# New_Project_2024-09-24_23-01-51.net
KiCad netlist of a schematic drawn in EasyEDA Pro
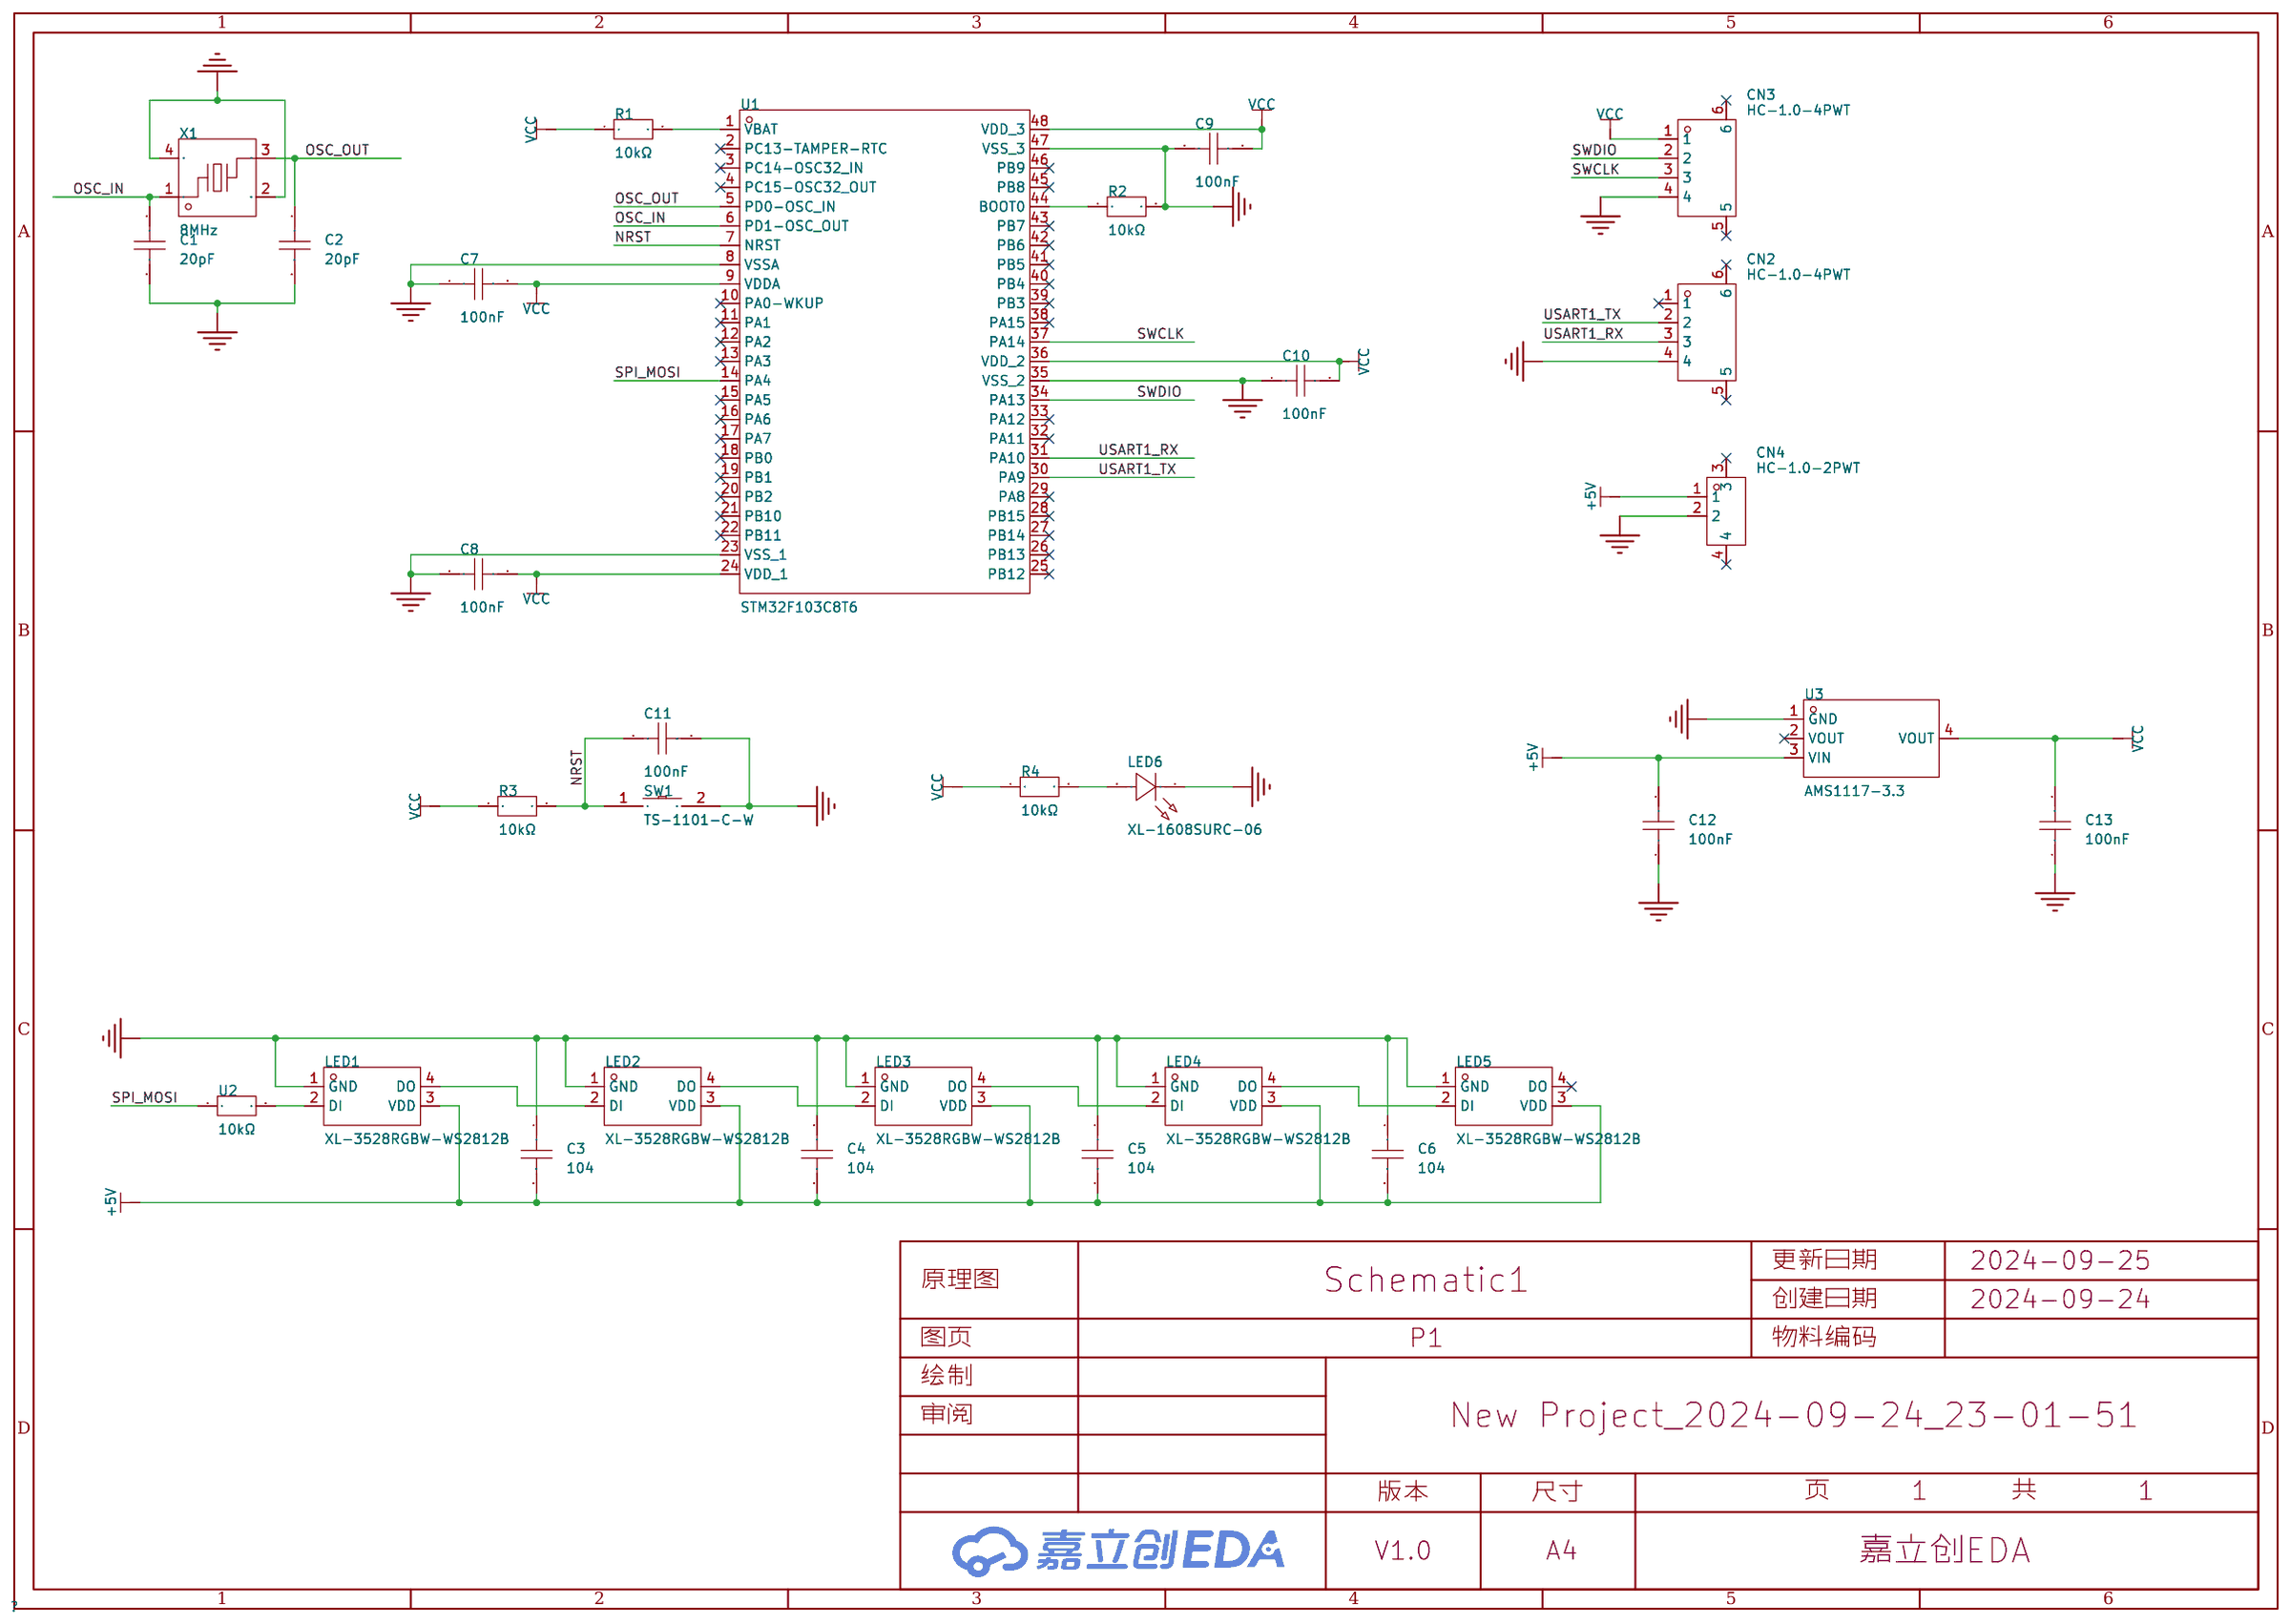
[diagram p0: schematic sheet]

(export (version "E")
  (design (tool "Eeschema 10.0.6"))
  (components
    (comp (ref "C1")
      (value "20pF")
      (footprint "easyedapro:C0603")
      (description "容值:100nF;精度:±10%;额定电压:50V;材质(温度系数):X7R;")
      (fields
        (field (name "Manufacturer Part") "CGA0603X7R104K500JT")
        (field (name "Manufacturer") "HRE(芯声)")
      )
      (libsource (lib "easyedapro") (part "CGA0603X7R104K500JT"))
    )
    (comp (ref "C2")
      (value "20pF")
      (footprint "easyedapro:C0603")
      (description "容值:100nF;精度:±10%;额定电压:50V;材质(温度系数):X7R;")
      (fields
        (field (name "Manufacturer Part") "CGA0603X7R104K500JT")
        (field (name "Manufacturer") "HRE(芯声)")
      )
      (libsource (lib "easyedapro") (part "CGA0603X7R104K500JT"))
    )
    (comp (ref "C3")
      (value "104")
      (footprint "easyedapro:C0603")
      (description "容值:100nF;精度:±10%;额定电压:50V;材质(温度系数):X7R;")
      (fields
        (field (name "Manufacturer Part") "CGA0603X7R104K500JT")
        (field (name "Manufacturer") "HRE(芯声)")
      )
      (libsource (lib "easyedapro") (part "CGA0603X7R104K500JT"))
    )
    (comp (ref "C4")
      (value "104")
      (footprint "easyedapro:C0603")
      (description "容值:100nF;精度:±10%;额定电压:50V;材质(温度系数):X7R;")
      (fields
        (field (name "Manufacturer Part") "CGA0603X7R104K500JT")
        (field (name "Manufacturer") "HRE(芯声)")
      )
      (libsource (lib "easyedapro") (part "CGA0603X7R104K500JT"))
    )
    (comp (ref "C5")
      (value "104")
      (footprint "easyedapro:C0603")
      (description "容值:100nF;精度:±10%;额定电压:50V;材质(温度系数):X7R;")
      (fields
        (field (name "Manufacturer Part") "CGA0603X7R104K500JT")
        (field (name "Manufacturer") "HRE(芯声)")
      )
      (libsource (lib "easyedapro") (part "CGA0603X7R104K500JT"))
    )
    (comp (ref "C6")
      (value "104")
      (footprint "easyedapro:C0603")
      (description "容值:100nF;精度:±10%;额定电压:50V;材质(温度系数):X7R;")
      (fields
        (field (name "Manufacturer Part") "CGA0603X7R104K500JT")
        (field (name "Manufacturer") "HRE(芯声)")
      )
      (libsource (lib "easyedapro") (part "CGA0603X7R104K500JT"))
    )
    (comp (ref "C7")
      (value "100nF")
      (footprint "easyedapro:C0603")
      (description "容值:100nF;精度:±10%;额定电压:50V;材质(温度系数):X7R;")
      (fields
        (field (name "Manufacturer Part") "CGA0603X7R104K500JT")
        (field (name "Manufacturer") "HRE(芯声)")
      )
      (libsource (lib "easyedapro") (part "CGA0603X7R104K500JT"))
    )
    (comp (ref "C8")
      (value "100nF")
      (footprint "easyedapro:C0603")
      (description "容值:100nF;精度:±10%;额定电压:50V;材质(温度系数):X7R;")
      (fields
        (field (name "Manufacturer Part") "CGA0603X7R104K500JT")
        (field (name "Manufacturer") "HRE(芯声)")
      )
      (libsource (lib "easyedapro") (part "CGA0603X7R104K500JT"))
    )
    (comp (ref "C9")
      (value "100nF")
      (footprint "easyedapro:C0603")
      (description "容值:100nF;精度:±10%;额定电压:50V;材质(温度系数):X7R;")
      (fields
        (field (name "Manufacturer Part") "CGA0603X7R104K500JT")
        (field (name "Manufacturer") "HRE(芯声)")
      )
      (libsource (lib "easyedapro") (part "CGA0603X7R104K500JT"))
    )
    (comp (ref "C10")
      (value "100nF")
      (footprint "easyedapro:C0603")
      (description "容值:100nF;精度:±10%;额定电压:50V;材质(温度系数):X7R;")
      (fields
        (field (name "Manufacturer Part") "CGA0603X7R104K500JT")
        (field (name "Manufacturer") "HRE(芯声)")
      )
      (libsource (lib "easyedapro") (part "CGA0603X7R104K500JT"))
    )
    (comp (ref "C11")
      (value "100nF")
      (footprint "easyedapro:C0603")
      (description "容值:100nF;精度:±10%;额定电压:50V;材质(温度系数):X7R;")
      (fields
        (field (name "Manufacturer Part") "CGA0603X7R104K500JT")
        (field (name "Manufacturer") "HRE(芯声)")
      )
      (libsource (lib "easyedapro") (part "CGA0603X7R104K500JT"))
    )
    (comp (ref "C12")
      (value "100nF")
      (footprint "easyedapro:C0603")
      (description "容值:100nF;精度:±10%;额定电压:50V;材质(温度系数):X7R;")
      (fields
        (field (name "Manufacturer Part") "CGA0603X7R104K500JT")
        (field (name "Manufacturer") "HRE(芯声)")
      )
      (libsource (lib "easyedapro") (part "CGA0603X7R104K500JT"))
    )
    (comp (ref "C13")
      (value "100nF")
      (footprint "easyedapro:C0603")
      (description "容值:100nF;精度:±10%;额定电压:50V;材质(温度系数):X7R;")
      (fields
        (field (name "Manufacturer Part") "CGA0603X7R104K500JT")
        (field (name "Manufacturer") "HRE(芯声)")
      )
      (libsource (lib "easyedapro") (part "CGA0603X7R104K500JT"))
    )
    (comp (ref "CN2")
      (value "HC-1.0-4PWT")
      (footprint "easyedapro:CONN-SMD_4P-P1.00_HCTL_HC-1.0-4PWT")
      (fields (field (name "Manufacturer") "HCTL(华灿天禄)"))
      (libsource (lib "easyedapro") (part "HC-1.0-4PWT"))
    )
    (comp (ref "CN3")
      (value "HC-1.0-4PWT")
      (footprint "easyedapro:CONN-SMD_4P-P1.00_HCTL_HC-1.0-4PWT")
      (fields (field (name "Manufacturer") "HCTL(华灿天禄)"))
      (libsource (lib "easyedapro") (part "HC-1.0-4PWT"))
    )
    (comp (ref "CN4")
      (value "HC-1.0-2PWT")
      (footprint "easyedapro:CONN-SMD_HC-1.0-2PWT")
      (fields (field (name "Manufacturer") "HCTL(华灿天禄)"))
      (libsource (lib "easyedapro") (part "HC-1.0-2PWT"))
    )
    (comp (ref "LED1")
      (value "XL-3528RGBW-WS2812B")
      (footprint "easyedapro:LED-SMD_4P-L3.5-W2.8-BR-1")
      (description "3528 七彩幻彩雾状 ws2812B 内置驱动IC")
      (fields (field (name "Manufacturer") "XINGLIGHT(成兴光)"))
      (libsource (lib "easyedapro") (part "XL-3528RGBW-WS2812B"))
    )
    (comp (ref "LED2")
      (value "XL-3528RGBW-WS2812B")
      (footprint "easyedapro:LED-SMD_4P-L3.5-W2.8-BR-1")
      (description "3528 七彩幻彩雾状 ws2812B 内置驱动IC")
      (fields (field (name "Manufacturer") "XINGLIGHT(成兴光)"))
      (libsource (lib "easyedapro") (part "XL-3528RGBW-WS2812B"))
    )
    (comp (ref "LED3")
      (value "XL-3528RGBW-WS2812B")
      (footprint "easyedapro:LED-SMD_4P-L3.5-W2.8-BR-1")
      (description "3528 七彩幻彩雾状 ws2812B 内置驱动IC")
      (fields (field (name "Manufacturer") "XINGLIGHT(成兴光)"))
      (libsource (lib "easyedapro") (part "XL-3528RGBW-WS2812B"))
    )
    (comp (ref "LED4")
      (value "XL-3528RGBW-WS2812B")
      (footprint "easyedapro:LED-SMD_4P-L3.5-W2.8-BR-1")
      (description "3528 七彩幻彩雾状 ws2812B 内置驱动IC")
      (fields (field (name "Manufacturer") "XINGLIGHT(成兴光)"))
      (libsource (lib "easyedapro") (part "XL-3528RGBW-WS2812B"))
    )
    (comp (ref "LED5")
      (value "XL-3528RGBW-WS2812B")
      (footprint "easyedapro:LED-SMD_4P-L3.5-W2.8-BR-1")
      (description "3528 七彩幻彩雾状 ws2812B 内置驱动IC")
      (fields (field (name "Manufacturer") "XINGLIGHT(成兴光)"))
      (libsource (lib "easyedapro") (part "XL-3528RGBW-WS2812B"))
    )
    (comp (ref "LED6")
      (value "XL-1608SURC-06")
      (footprint "easyedapro:LED0603-RD_RED")
      (description "发光颜色:红色;功率:55mW;正向电流:25mA;主波长:617nm~621nm;透镜颜色:无色透明透镜;色温:-;发光角度:120°;载带方式:正贴;工作温度:-30°C~+85°C;")
      (fields (field (name "Manufacturer") "XINGLIGHT(成兴光)"))
      (libsource (lib "easyedapro") (part "XL-1608SURC-06"))
    )
    (comp (ref "R1")
      (value "10kΩ")
      (footprint "easyedapro:R0603")
      (description "电阻类型:厚膜电阻;阻值:4.7kΩ;精度:±5%;功率:100mW;最大工作电压:75V;温度系数:±100ppm/°C;")
      (fields (field (name "Manufacturer Part") "FRC0603J472 TS") (field (name "Manufacturer") "FOJAN(富捷)"))
      (libsource (lib "easyedapro") (part "FRC0603J472 TS"))
    )
    (comp (ref "R2")
      (value "10kΩ")
      (footprint "easyedapro:R0603")
      (description "电阻类型:厚膜电阻;阻值:4.7kΩ;精度:±5%;功率:100mW;最大工作电压:75V;温度系数:±100ppm/°C;")
      (fields (field (name "Manufacturer Part") "FRC0603J472 TS") (field (name "Manufacturer") "FOJAN(富捷)"))
      (libsource (lib "easyedapro") (part "FRC0603J472 TS"))
    )
    (comp (ref "R3")
      (value "10kΩ")
      (footprint "easyedapro:R0603")
      (description "电阻类型:厚膜电阻;阻值:4.7kΩ;精度:±5%;功率:100mW;最大工作电压:75V;温度系数:±100ppm/°C;")
      (fields (field (name "Manufacturer Part") "FRC0603J472 TS") (field (name "Manufacturer") "FOJAN(富捷)"))
      (libsource (lib "easyedapro") (part "FRC0603J472 TS"))
    )
    (comp (ref "R4")
      (value "10kΩ")
      (footprint "easyedapro:R0603")
      (description "电阻类型:厚膜电阻;阻值:4.7kΩ;精度:±5%;功率:100mW;最大工作电压:75V;温度系数:±100ppm/°C;")
      (fields (field (name "Manufacturer Part") "FRC0603J472 TS") (field (name "Manufacturer") "FOJAN(富捷)"))
      (libsource (lib "easyedapro") (part "FRC0603J472 TS"))
    )
    (comp (ref "SW1")
      (value "TS-1101-C-W")
      (footprint "easyedapro:SW-SMD_L6.0-W3.3-LS8.0")
      (fields (field (name "Manufacturer") "XKB Connectivity(中国星坤)"))
      (libsource (lib "easyedapro") (part "TS-1101-C-W"))
    )
    (comp (ref "U1")
      (value "STM32F103C8T6")
      (footprint "easyedapro:LQFP-48_L7.0-W7.0-P0.50-LS9.0-BL")
      (description "CPU内核:ARM-M3;程序存储容量:64KB;RAM总容量:20KB;GPIO端口数量:37;工作电压范围:2V~3.6V;CPU最大主频:72MHz;程序存储器类型:FLASH;")
      (fields (field (name "Manufacturer") "ST(意法半导体)"))
      (libsource (lib "easyedapro") (part "STM32F103C8T6"))
    )
    (comp (ref "U2")
      (value "10kΩ")
      (footprint "easyedapro:R0603")
      (description "电阻类型:厚膜电阻;阻值:390kΩ;精度:±1%;功率:100mW;最大工作电压:75V;温度系数:±100ppm/°C;")
      (fields (field (name "Manufacturer Part") "FRC0603F3903TS") (field (name "Manufacturer") "FOJAN(富捷)"))
      (libsource (lib "easyedapro") (part "FRC0603F3903TS"))
    )
    (comp (ref "U3")
      (value "AMS1117-3.3")
      (footprint "easyedapro:SOT-223-3_L6.5-W3.4-P2.30-LS7.0-BR")
      (description "输出类型:固定;最大输入电压:-;输出电压:3.3V;最大输出电流:1A;电源纹波抑制比(PSRR):72dB@(120Hz);输出极性:正极;")
      (fields (field (name "Manufacturer") "AMS"))
      (libsource (lib "easyedapro") (part "AMS1117-3.3"))
    )
    (comp (ref "X1")
      (value "8MHz")
      (footprint "easyedapro:OSC-SMD_4P-L3.2-W2.5-BL")
      (description "晶振类型:贴片晶振;频率:8MHz;常温频差:±10ppm;外接负载电容:12pF;频率稳定度(全温):±20ppm;")
      (fields (field (name "Manufacturer Part") "X32258MOB4SI") (field (name "Manufacturer") "YXC(扬兴晶振)"))
      (libsource (lib "easyedapro") (part "x32258mob4si"))
    )
  )
  (nets
    (net (code "1") (name "+5V") (class "Default")
      (node (ref "C12") (pin "2") (pinfunction "2_2") (pintype "unspecified"))
      (node (ref "C3") (pin "2") (pinfunction "2_2") (pintype "unspecified"))
      (node (ref "C4") (pin "2") (pinfunction "2_2") (pintype "unspecified"))
      (node (ref "C5") (pin "2") (pinfunction "2_2") (pintype "unspecified"))
      (node (ref "C6") (pin "2") (pinfunction "2_2") (pintype "unspecified"))
      (node (ref "CN4") (pin "1") (pinfunction "1_1") (pintype "unspecified"))
      (node (ref "LED1") (pin "3") (pinfunction "VDD_3") (pintype "unspecified"))
      (node (ref "LED2") (pin "3") (pinfunction "VDD_3") (pintype "unspecified"))
      (node (ref "LED3") (pin "3") (pinfunction "VDD_3") (pintype "unspecified"))
      (node (ref "LED4") (pin "3") (pinfunction "VDD_3") (pintype "unspecified"))
      (node (ref "LED5") (pin "3") (pinfunction "VDD_3") (pintype "unspecified"))
      (node (ref "U3") (pin "3") (pinfunction "VIN_3") (pintype "unspecified"))
    )
    (net (code "2") (name "/NRST") (class "Default")
      (node (ref "C11") (pin "1") (pinfunction "1_1") (pintype "unspecified"))
      (node (ref "R3") (pin "2") (pinfunction "2_2") (pintype "unspecified"))
      (node (ref "SW1") (pin "1") (pinfunction "1_1") (pintype "unspecified"))
      (node (ref "U1") (pin "7") (pinfunction "NRST_7") (pintype "unspecified"))
    )
    (net (code "3") (name "/OSC_IN") (class "Default")
      (node (ref "C1") (pin "1") (pinfunction "1_1") (pintype "unspecified"))
      (node (ref "U1") (pin "6") (pinfunction "PD1-OSC_OUT_6") (pintype "unspecified"))
      (node (ref "X1") (pin "1") (pinfunction "1_1") (pintype "input"))
    )
    (net (code "4") (name "/OSC_OUT") (class "Default")
      (node (ref "C2") (pin "1") (pinfunction "1_1") (pintype "unspecified"))
      (node (ref "U1") (pin "5") (pinfunction "PD0-OSC_IN_5") (pintype "unspecified"))
      (node (ref "X1") (pin "3") (pinfunction "3_3") (pintype "input"))
    )
    (net (code "5") (name "/SPI_MOSI") (class "Default")
      (node (ref "U1") (pin "14") (pinfunction "PA4_14") (pintype "unspecified"))
      (node (ref "U2") (pin "1") (pinfunction "1_1") (pintype "unspecified"))
    )
    (net (code "6") (name "/SWCLK") (class "Default")
      (node (ref "CN3") (pin "3") (pinfunction "3_3") (pintype "unspecified"))
      (node (ref "U1") (pin "37") (pinfunction "PA14_37") (pintype "unspecified"))
    )
    (net (code "7") (name "/SWDIO") (class "Default")
      (node (ref "CN3") (pin "2") (pinfunction "2_2") (pintype "unspecified"))
      (node (ref "U1") (pin "34") (pinfunction "PA13_34") (pintype "unspecified"))
    )
    (net (code "8") (name "/USART1_RX") (class "Default")
      (node (ref "CN2") (pin "3") (pinfunction "3_3") (pintype "unspecified"))
      (node (ref "U1") (pin "31") (pinfunction "PA10_31") (pintype "unspecified"))
    )
    (net (code "9") (name "/USART1_TX") (class "Default")
      (node (ref "CN2") (pin "2") (pinfunction "2_2") (pintype "unspecified"))
      (node (ref "U1") (pin "30") (pinfunction "PA9_30") (pintype "unspecified"))
    )
    (net (code "10") (name "GND") (class "Default")
      (node (ref "C1") (pin "2") (pinfunction "2_2") (pintype "unspecified"))
      (node (ref "C10") (pin "1") (pinfunction "1_1") (pintype "unspecified"))
      (node (ref "C11") (pin "2") (pinfunction "2_2") (pintype "unspecified"))
      (node (ref "C12") (pin "1") (pinfunction "1_1") (pintype "unspecified"))
      (node (ref "C13") (pin "1") (pinfunction "1_1") (pintype "unspecified"))
      (node (ref "C2") (pin "2") (pinfunction "2_2") (pintype "unspecified"))
      (node (ref "C3") (pin "1") (pinfunction "1_1") (pintype "unspecified"))
      (node (ref "C4") (pin "1") (pinfunction "1_1") (pintype "unspecified"))
      (node (ref "C5") (pin "1") (pinfunction "1_1") (pintype "unspecified"))
      (node (ref "C6") (pin "1") (pinfunction "1_1") (pintype "unspecified"))
      (node (ref "C7") (pin "1") (pinfunction "1_1") (pintype "unspecified"))
      (node (ref "C8") (pin "1") (pinfunction "1_1") (pintype "unspecified"))
      (node (ref "C9") (pin "1") (pinfunction "1_1") (pintype "unspecified"))
      (node (ref "CN2") (pin "4") (pinfunction "4_4") (pintype "unspecified"))
      (node (ref "CN3") (pin "4") (pinfunction "4_4") (pintype "unspecified"))
      (node (ref "CN4") (pin "2") (pinfunction "2_2") (pintype "unspecified"))
      (node (ref "LED1") (pin "1") (pinfunction "GND_1") (pintype "unspecified"))
      (node (ref "LED2") (pin "1") (pinfunction "GND_1") (pintype "unspecified"))
      (node (ref "LED3") (pin "1") (pinfunction "GND_1") (pintype "unspecified"))
      (node (ref "LED4") (pin "1") (pinfunction "GND_1") (pintype "unspecified"))
      (node (ref "LED5") (pin "1") (pinfunction "GND_1") (pintype "unspecified"))
      (node (ref "LED6") (pin "1") (pinfunction "K_1") (pintype "unspecified"))
      (node (ref "R2") (pin "2") (pinfunction "2_2") (pintype "unspecified"))
      (node (ref "SW1") (pin "2") (pinfunction "2_2") (pintype "unspecified"))
      (node (ref "U1") (pin "23") (pinfunction "VSS_1_23") (pintype "unspecified"))
      (node (ref "U1") (pin "35") (pinfunction "VSS_2_35") (pintype "unspecified"))
      (node (ref "U1") (pin "47") (pinfunction "VSS_3_47") (pintype "unspecified"))
      (node (ref "U1") (pin "8") (pinfunction "VSSA_8") (pintype "unspecified"))
      (node (ref "U3") (pin "1") (pinfunction "GND_1") (pintype "unspecified"))
      (node (ref "X1") (pin "2") (pinfunction "GND_2") (pintype "input"))
      (node (ref "X1") (pin "4") (pinfunction "GND_4") (pintype "input"))
    )
    (net (code "11") (name "Net-(LED1-DI)") (class "Default")
      (node (ref "LED1") (pin "2") (pinfunction "DI_2") (pintype "unspecified"))
      (node (ref "U2") (pin "2") (pinfunction "2_2") (pintype "unspecified"))
    )
    (net (code "12") (name "Net-(LED1-DO)") (class "Default")
      (node (ref "LED1") (pin "4") (pinfunction "DO_4") (pintype "unspecified"))
      (node (ref "LED2") (pin "2") (pinfunction "DI_2") (pintype "unspecified"))
    )
    (net (code "13") (name "Net-(LED2-DO)") (class "Default")
      (node (ref "LED2") (pin "4") (pinfunction "DO_4") (pintype "unspecified"))
      (node (ref "LED3") (pin "2") (pinfunction "DI_2") (pintype "unspecified"))
    )
    (net (code "14") (name "Net-(LED3-DO)") (class "Default")
      (node (ref "LED3") (pin "4") (pinfunction "DO_4") (pintype "unspecified"))
      (node (ref "LED4") (pin "2") (pinfunction "DI_2") (pintype "unspecified"))
    )
    (net (code "15") (name "Net-(LED4-DO)") (class "Default")
      (node (ref "LED4") (pin "4") (pinfunction "DO_4") (pintype "unspecified"))
      (node (ref "LED5") (pin "2") (pinfunction "DI_2") (pintype "unspecified"))
    )
    (net (code "16") (name "Net-(LED6-A)") (class "Default")
      (node (ref "LED6") (pin "2") (pinfunction "A_2") (pintype "unspecified"))
      (node (ref "R4") (pin "2") (pinfunction "2_2") (pintype "unspecified"))
    )
    (net (code "17") (name "Net-(U1-BOOT0)") (class "Default")
      (node (ref "R2") (pin "1") (pinfunction "1_1") (pintype "unspecified"))
      (node (ref "U1") (pin "44") (pinfunction "BOOT0_44") (pintype "unspecified"))
    )
    (net (code "18") (name "Net-(U1-VBAT)") (class "Default")
      (node (ref "R1") (pin "2") (pinfunction "2_2") (pintype "unspecified"))
      (node (ref "U1") (pin "1") (pinfunction "VBAT_1") (pintype "unspecified"))
    )
    (net (code "19") (name "VCC") (class "Default")
      (node (ref "C10") (pin "2") (pinfunction "2_2") (pintype "unspecified"))
      (node (ref "C13") (pin "2") (pinfunction "2_2") (pintype "unspecified"))
      (node (ref "C7") (pin "2") (pinfunction "2_2") (pintype "unspecified"))
      (node (ref "C8") (pin "2") (pinfunction "2_2") (pintype "unspecified"))
      (node (ref "C9") (pin "2") (pinfunction "2_2") (pintype "unspecified"))
      (node (ref "CN3") (pin "1") (pinfunction "1_1") (pintype "unspecified"))
      (node (ref "R1") (pin "1") (pinfunction "1_1") (pintype "unspecified"))
      (node (ref "R3") (pin "1") (pinfunction "1_1") (pintype "unspecified"))
      (node (ref "R4") (pin "1") (pinfunction "1_1") (pintype "unspecified"))
      (node (ref "U1") (pin "24") (pinfunction "VDD_1_24") (pintype "unspecified"))
      (node (ref "U1") (pin "36") (pinfunction "VDD_2_36") (pintype "unspecified"))
      (node (ref "U1") (pin "48") (pinfunction "VDD_3_48") (pintype "unspecified"))
      (node (ref "U1") (pin "9") (pinfunction "VDDA_9") (pintype "unspecified"))
      (node (ref "U3") (pin "4") (pinfunction "VOUT_4") (pintype "unspecified"))
    )
    (net (code "20") (name "unconnected-(CN2-Pad1)") (class "Default")
      (node (ref "CN2") (pin "1") (pinfunction "1_1") (pintype "unspecified+no_connect"))
    )
    (net (code "21") (name "unconnected-(CN2-Pad5)") (class "Default")
      (node (ref "CN2") (pin "5") (pinfunction "5_5") (pintype "unspecified+no_connect"))
    )
    (net (code "22") (name "unconnected-(CN2-Pad6)") (class "Default")
      (node (ref "CN2") (pin "6") (pinfunction "6_6") (pintype "unspecified+no_connect"))
    )
    (net (code "23") (name "unconnected-(CN3-Pad5)") (class "Default")
      (node (ref "CN3") (pin "5") (pinfunction "5_5") (pintype "unspecified+no_connect"))
    )
    (net (code "24") (name "unconnected-(CN3-Pad6)") (class "Default")
      (node (ref "CN3") (pin "6") (pinfunction "6_6") (pintype "unspecified+no_connect"))
    )
    (net (code "25") (name "unconnected-(CN4-Pad3)") (class "Default")
      (node (ref "CN4") (pin "3") (pinfunction "3_3") (pintype "unspecified+no_connect"))
    )
    (net (code "26") (name "unconnected-(CN4-Pad4)") (class "Default")
      (node (ref "CN4") (pin "4") (pinfunction "4_4") (pintype "unspecified+no_connect"))
    )
    (net (code "27") (name "unconnected-(LED5-DO-Pad4)") (class "Default")
      (node (ref "LED5") (pin "4") (pinfunction "DO_4") (pintype "unspecified+no_connect"))
    )
    (net (code "28") (name "unconnected-(U1-PA0-WKUP-Pad10)") (class "Default")
      (node (ref "U1") (pin "10") (pinfunction "PA0-WKUP_10") (pintype "unspecified+no_connect"))
    )
    (net (code "29") (name "unconnected-(U1-PA1-Pad11)") (class "Default")
      (node (ref "U1") (pin "11") (pinfunction "PA1_11") (pintype "unspecified+no_connect"))
    )
    (net (code "30") (name "unconnected-(U1-PA2-Pad12)") (class "Default")
      (node (ref "U1") (pin "12") (pinfunction "PA2_12") (pintype "unspecified+no_connect"))
    )
    (net (code "31") (name "unconnected-(U1-PA3-Pad13)") (class "Default")
      (node (ref "U1") (pin "13") (pinfunction "PA3_13") (pintype "unspecified+no_connect"))
    )
    (net (code "32") (name "unconnected-(U1-PA5-Pad15)") (class "Default")
      (node (ref "U1") (pin "15") (pinfunction "PA5_15") (pintype "unspecified+no_connect"))
    )
    (net (code "33") (name "unconnected-(U1-PA6-Pad16)") (class "Default")
      (node (ref "U1") (pin "16") (pinfunction "PA6_16") (pintype "unspecified+no_connect"))
    )
    (net (code "34") (name "unconnected-(U1-PA7-Pad17)") (class "Default")
      (node (ref "U1") (pin "17") (pinfunction "PA7_17") (pintype "unspecified+no_connect"))
    )
    (net (code "35") (name "unconnected-(U1-PA8-Pad29)") (class "Default")
      (node (ref "U1") (pin "29") (pinfunction "PA8_29") (pintype "unspecified+no_connect"))
    )
    (net (code "36") (name "unconnected-(U1-PA11-Pad32)") (class "Default")
      (node (ref "U1") (pin "32") (pinfunction "PA11_32") (pintype "unspecified+no_connect"))
    )
    (net (code "37") (name "unconnected-(U1-PA12-Pad33)") (class "Default")
      (node (ref "U1") (pin "33") (pinfunction "PA12_33") (pintype "unspecified+no_connect"))
    )
    (net (code "38") (name "unconnected-(U1-PA15-Pad38)") (class "Default")
      (node (ref "U1") (pin "38") (pinfunction "PA15_38") (pintype "unspecified+no_connect"))
    )
    (net (code "39") (name "unconnected-(U1-PB0-Pad18)") (class "Default")
      (node (ref "U1") (pin "18") (pinfunction "PB0_18") (pintype "unspecified+no_connect"))
    )
    (net (code "40") (name "unconnected-(U1-PB1-Pad19)") (class "Default")
      (node (ref "U1") (pin "19") (pinfunction "PB1_19") (pintype "unspecified+no_connect"))
    )
    (net (code "41") (name "unconnected-(U1-PB2-Pad20)") (class "Default")
      (node (ref "U1") (pin "20") (pinfunction "PB2_20") (pintype "unspecified+no_connect"))
    )
    (net (code "42") (name "unconnected-(U1-PB3-Pad39)") (class "Default")
      (node (ref "U1") (pin "39") (pinfunction "PB3_39") (pintype "unspecified+no_connect"))
    )
    (net (code "43") (name "unconnected-(U1-PB4-Pad40)") (class "Default")
      (node (ref "U1") (pin "40") (pinfunction "PB4_40") (pintype "unspecified+no_connect"))
    )
    (net (code "44") (name "unconnected-(U1-PB5-Pad41)") (class "Default")
      (node (ref "U1") (pin "41") (pinfunction "PB5_41") (pintype "unspecified+no_connect"))
    )
    (net (code "45") (name "unconnected-(U1-PB6-Pad42)") (class "Default")
      (node (ref "U1") (pin "42") (pinfunction "PB6_42") (pintype "unspecified+no_connect"))
    )
    (net (code "46") (name "unconnected-(U1-PB7-Pad43)") (class "Default")
      (node (ref "U1") (pin "43") (pinfunction "PB7_43") (pintype "unspecified+no_connect"))
    )
    (net (code "47") (name "unconnected-(U1-PB8-Pad45)") (class "Default")
      (node (ref "U1") (pin "45") (pinfunction "PB8_45") (pintype "unspecified+no_connect"))
    )
    (net (code "48") (name "unconnected-(U1-PB9-Pad46)") (class "Default")
      (node (ref "U1") (pin "46") (pinfunction "PB9_46") (pintype "unspecified+no_connect"))
    )
    (net (code "49") (name "unconnected-(U1-PB10-Pad21)") (class "Default")
      (node (ref "U1") (pin "21") (pinfunction "PB10_21") (pintype "unspecified+no_connect"))
    )
    (net (code "50") (name "unconnected-(U1-PB11-Pad22)") (class "Default")
      (node (ref "U1") (pin "22") (pinfunction "PB11_22") (pintype "unspecified+no_connect"))
    )
    (net (code "51") (name "unconnected-(U1-PB12-Pad25)") (class "Default")
      (node (ref "U1") (pin "25") (pinfunction "PB12_25") (pintype "unspecified+no_connect"))
    )
    (net (code "52") (name "unconnected-(U1-PB13-Pad26)") (class "Default")
      (node (ref "U1") (pin "26") (pinfunction "PB13_26") (pintype "unspecified+no_connect"))
    )
    (net (code "53") (name "unconnected-(U1-PB14-Pad27)") (class "Default")
      (node (ref "U1") (pin "27") (pinfunction "PB14_27") (pintype "unspecified+no_connect"))
    )
    (net (code "54") (name "unconnected-(U1-PB15-Pad28)") (class "Default")
      (node (ref "U1") (pin "28") (pinfunction "PB15_28") (pintype "unspecified+no_connect"))
    )
    (net (code "55") (name "unconnected-(U1-PC13-TAMPER-RTC-Pad2)") (class "Default")
      (node (ref "U1") (pin "2") (pinfunction "PC13-TAMPER-RTC_2") (pintype "unspecified+no_connect"))
    )
    (net (code "56") (name "unconnected-(U1-PC14-OSC32_IN-Pad3)") (class "Default")
      (node (ref "U1") (pin "3") (pinfunction "PC14-OSC32_IN_3") (pintype "unspecified+no_connect"))
    )
    (net (code "57") (name "unconnected-(U1-PC15-OSC32_OUT-Pad4)") (class "Default")
      (node (ref "U1") (pin "4") (pinfunction "PC15-OSC32_OUT_4") (pintype "unspecified+no_connect"))
    )
    (net (code "58") (name "unconnected-(U3-VOUT-Pad2)") (class "Default")
      (node (ref "U3") (pin "2") (pinfunction "VOUT_2") (pintype "unspecified+no_connect"))
    )
  )
)
